# pmon_3v8.net
KiCad netlist of a schematic drawn in EAGLE
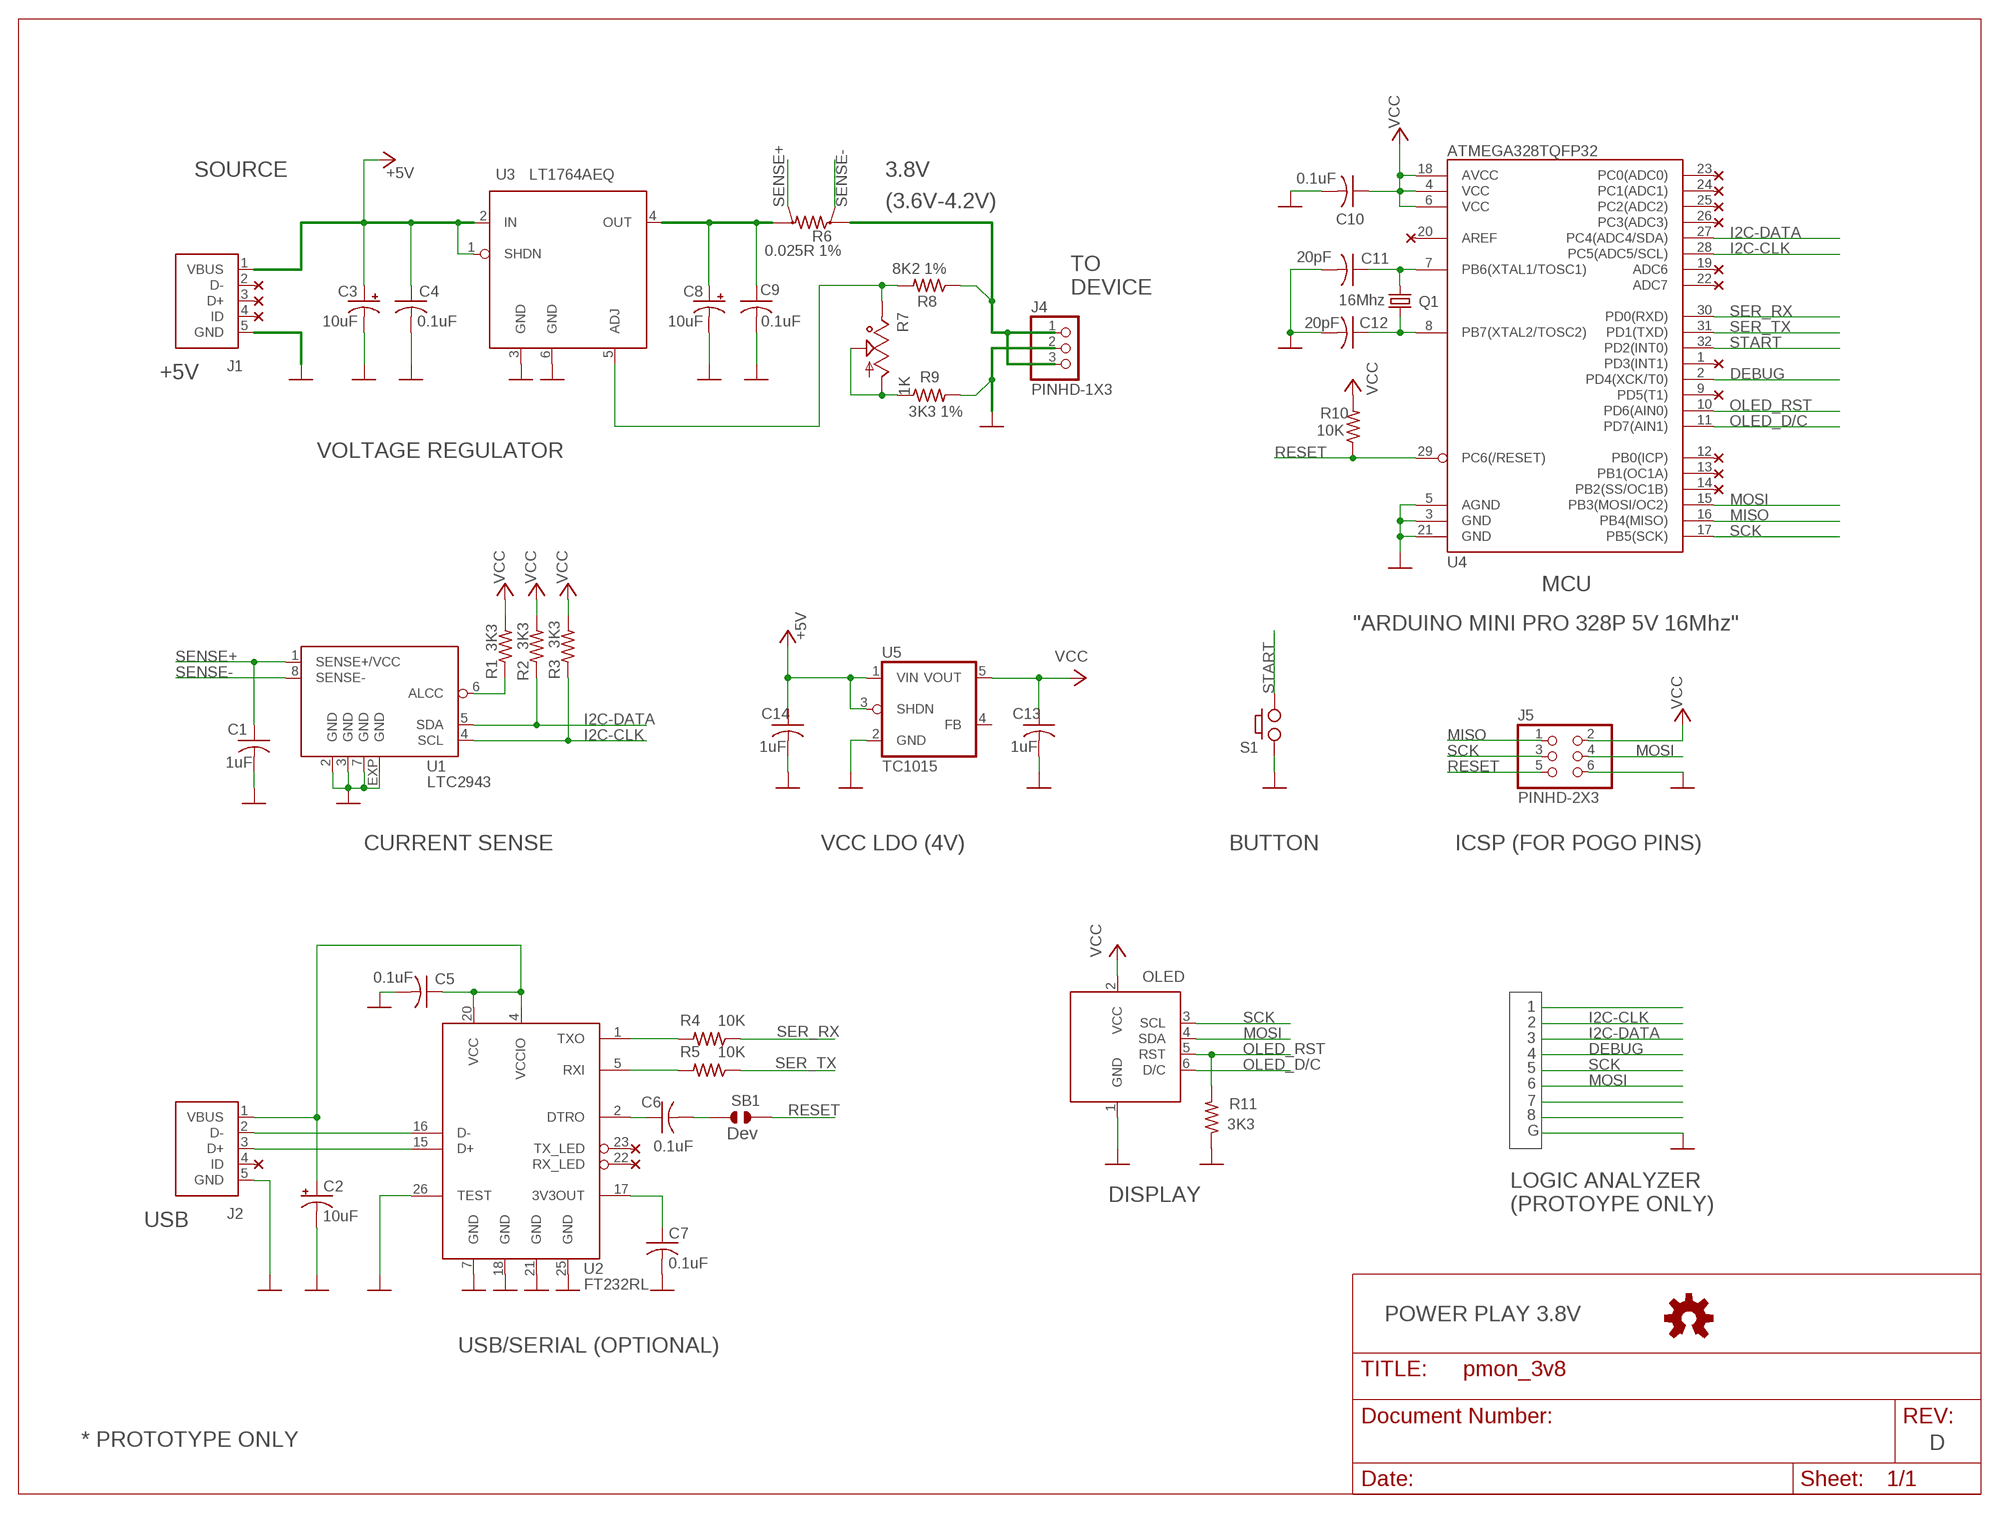
[diagram p0: schematic, sheet 1]

(export (version "E")
  (design (tool "Eeschema 10.0.6"))
  (components
    (comp (ref "C1")
      (value "1uF")
      (footprint "eagle-import:C0603")
      (libsource (lib "eagle-import") (part "CAP-C0603"))
    )
    (comp (ref "C2")
      (value "10uF")
      (footprint "eagle-import:A_3216-18R")
      (libsource (lib "eagle-import") (part "CPOL-USA/3216-18R"))
    )
    (comp (ref "C3")
      (value "10uF")
      (footprint "eagle-import:A_3216-18R")
      (libsource (lib "eagle-import") (part "CPOL-USA/3216-18R"))
    )
    (comp (ref "C4")
      (value "0.1uF")
      (footprint "eagle-import:C0603")
      (libsource (lib "eagle-import") (part "CAP-C0603"))
    )
    (comp (ref "C5")
      (value "0.1uF")
      (footprint "eagle-import:C0603")
      (libsource (lib "eagle-import") (part "CAP-C0603"))
    )
    (comp (ref "C6")
      (value "0.1uF")
      (footprint "eagle-import:C0603")
      (libsource (lib "eagle-import") (part "CAP-C0603"))
    )
    (comp (ref "C7")
      (value "0.1uF")
      (footprint "eagle-import:C0603")
      (libsource (lib "eagle-import") (part "CAP-C0603"))
    )
    (comp (ref "C8")
      (value "10uF")
      (footprint "eagle-import:A_3216-18R")
      (libsource (lib "eagle-import") (part "CPOL-USA/3216-18R"))
    )
    (comp (ref "C9")
      (value "0.1uF")
      (footprint "eagle-import:C0603")
      (libsource (lib "eagle-import") (part "CAP-C0603"))
    )
    (comp (ref "C10")
      (value "0.1uF")
      (footprint "eagle-import:C0603")
      (libsource (lib "eagle-import") (part "CAP-C0603"))
    )
    (comp (ref "C11")
      (value "20pF")
      (footprint "eagle-import:C0603")
      (libsource (lib "eagle-import") (part "CAP-C0603"))
    )
    (comp (ref "C12")
      (value "20pF")
      (footprint "eagle-import:C0603")
      (libsource (lib "eagle-import") (part "CAP-C0603"))
    )
    (comp (ref "C13")
      (value "1uF")
      (footprint "eagle-import:C0603")
      (libsource (lib "eagle-import") (part "CAP-C0603"))
    )
    (comp (ref "C14")
      (value "1uF")
      (footprint "eagle-import:C0603")
      (libsource (lib "eagle-import") (part "CAP-C0603"))
    )
    (comp (ref "J1")
      (value "USB")
      (footprint "eagle-import:USB-MICRO-ZX62RD-AB-5P8")
      (libsource (lib "eagle-import") (part "USB"))
    )
    (comp (ref "J2")
      (value "USB")
      (footprint "eagle-import:USB-MICRO-ZX62RD-AB-5P8")
      (libsource (lib "eagle-import") (part "USB"))
    )
    (comp (ref "J4")
      (value "PINHD-1X3")
      (footprint "eagle-import:1X03")
      (libsource (lib "eagle-import") (part "PINHD-1X3"))
    )
    (comp (ref "J5")
      (value "PINHD-2X3")
      (footprint "eagle-import:2X03")
      (libsource (lib "eagle-import") (part "PINHD-2X3"))
    )
    (comp (ref "OLED")
      (value "OLED")
      (footprint "eagle-import:OLED")
      (libsource (lib "eagle-import") (part "OLED"))
    )
    (comp (ref "Q1")
      (value "16Mhz")
      (footprint "eagle-import:CRYSTAL-CTS406")
      (libsource (lib "eagle-import") (part "CRYSTALCTS406"))
    )
    (comp (ref "R1")
      (value "3K3")
      (footprint "eagle-import:R0603")
      (libsource (lib "eagle-import") (part "RES-R0603"))
    )
    (comp (ref "R2")
      (value "3K3")
      (footprint "eagle-import:R0603")
      (libsource (lib "eagle-import") (part "RES-R0603"))
    )
    (comp (ref "R3")
      (value "3K3")
      (footprint "eagle-import:R0603")
      (libsource (lib "eagle-import") (part "RES-R0603"))
    )
    (comp (ref "R4")
      (value "10K")
      (footprint "eagle-import:R0603")
      (libsource (lib "eagle-import") (part "RES-R0603"))
    )
    (comp (ref "R5")
      (value "10K")
      (footprint "eagle-import:R0603")
      (libsource (lib "eagle-import") (part "RES-R0603"))
    )
    (comp (ref "R6")
      (value "0.025R 1%")
      (footprint "eagle-import:KELVIN-6432")
      (libsource (lib "eagle-import") (part "RES-SHUNT-6432"))
    )
    (comp (ref "R7")
      (value "1K")
      (footprint "eagle-import:TRIM-POT_SM-42_43A")
      (libsource (lib "eagle-import") (part "TRIM_US-SM-42/43A"))
    )
    (comp (ref "R8")
      (value "8K2 1%")
      (footprint "eagle-import:R0603")
      (libsource (lib "eagle-import") (part "RES-R0603"))
    )
    (comp (ref "R9")
      (value "3K3 1%")
      (footprint "eagle-import:R0603")
      (libsource (lib "eagle-import") (part "RES-R0603"))
    )
    (comp (ref "R10")
      (value "10K")
      (footprint "eagle-import:R0603")
      (libsource (lib "eagle-import") (part "RES-R0603"))
    )
    (comp (ref "R11")
      (value "3K3")
      (footprint "eagle-import:R0603")
      (libsource (lib "eagle-import") (part "RES-R0603"))
    )
    (comp (ref "S1")
      (value "PUSH_BUTTON")
      (footprint "eagle-import:TLE1105")
      (libsource (lib "eagle-import") (part "PUSH_BUTTON"))
    )
    (comp (ref "SB1")
      (value "JUMPER_SOLDER_1X2")
      (footprint "eagle-import:JUMPER_SOLDER_1X2")
      (libsource (lib "eagle-import") (part "JUMPER_SOLDER_1X2"))
    )
    (comp (ref "U$28")
      (value "OSH")
      (footprint "eagle-import:OSH")
      (libsource (lib "eagle-import") (part "OSH"))
    )
    (comp (ref "U1")
      (value "LTC2943")
      (footprint "eagle-import:DFN8-3X3")
      (libsource (lib "eagle-import") (part "LTC2943"))
    )
    (comp (ref "U2")
      (value "FT232RL")
      (footprint "eagle-import:SSOP28DB")
      (libsource (lib "eagle-import") (part "FT232RL"))
    )
    (comp (ref "U3")
      (value "LT1764AEQ")
      (footprint "eagle-import:TO263-5")
      (libsource (lib "eagle-import") (part "LTE1764"))
    )
    (comp (ref "U4")
      (value "ATMEGA328TQFP32")
      (footprint "eagle-import:TQFP32-08")
      (libsource (lib "eagle-import") (part "ATMEGA328TQFP32"))
    )
    (comp (ref "U5")
      (value "TC1015")
      (footprint "eagle-import:SOT25")
      (libsource (lib "eagle-import") (part "TC1015"))
    )
  )
  (nets
    (net (code "1") (name "+5V") (class "Default")
      (node (ref "C14") (pin "1") (pinfunction "1_1") (pintype "passive"))
      (node (ref "C3") (pin "+") (pinfunction "+_+") (pintype "passive"))
      (node (ref "C4") (pin "1") (pinfunction "1_1") (pintype "passive"))
      (node (ref "J1") (pin "1") (pinfunction "VBUS_1") (pintype "bidirectional"))
      (node (ref "U3") (pin "1") (pinfunction "SHDN_1") (pintype "bidirectional"))
      (node (ref "U3") (pin "2") (pinfunction "IN_2") (pintype "bidirectional"))
      (node (ref "U5") (pin "1") (pinfunction "VIN_1") (pintype "power_in"))
      (node (ref "U5") (pin "3") (pinfunction "SHDN_3") (pintype "input"))
    )
    (net (code "2") (name "/AREF") (class "Default")
      (node (ref "U4") (pin "20") (pinfunction "AREF_20") (pintype "power_in"))
    )
    (net (code "3") (name "/DEBUG") (class "Default")
      (node (ref "U4") (pin "2") (pinfunction "PD4(XCK/T0)_2") (pintype "bidirectional"))
    )
    (net (code "4") (name "/I2C-CLK") (class "Default")
      (node (ref "R3") (pin "1") (pinfunction "1_1") (pintype "passive"))
      (node (ref "U1") (pin "4") (pinfunction "SCL_4") (pintype "input"))
      (node (ref "U4") (pin "28") (pinfunction "PC5(ADC5/SCL)_28") (pintype "bidirectional"))
    )
    (net (code "5") (name "/I2C-DATA") (class "Default")
      (node (ref "R2") (pin "1") (pinfunction "1_1") (pintype "passive"))
      (node (ref "U1") (pin "5") (pinfunction "SDA_5") (pintype "bidirectional"))
      (node (ref "U4") (pin "27") (pinfunction "PC4(ADC4/SDA)_27") (pintype "bidirectional"))
    )
    (net (code "6") (name "/MISO") (class "Default")
      (node (ref "J5") (pin "1") (pinfunction "1_1") (pintype "passive"))
      (node (ref "U4") (pin "16") (pinfunction "PB4(MISO)_16") (pintype "bidirectional"))
    )
    (net (code "7") (name "/MOSI") (class "Default")
      (node (ref "J5") (pin "4") (pinfunction "4_4") (pintype "passive"))
      (node (ref "OLED") (pin "4") (pinfunction "SDA_4") (pintype "input"))
      (node (ref "U4") (pin "15") (pinfunction "PB3(MOSI/OC2)_15") (pintype "bidirectional"))
    )
    (net (code "8") (name "/OLED_D{slash}C") (class "Default")
      (node (ref "OLED") (pin "6") (pinfunction "D/C_6") (pintype "input"))
      (node (ref "U4") (pin "11") (pinfunction "PD7(AIN1)_11") (pintype "bidirectional"))
    )
    (net (code "9") (name "/OLED_RST") (class "Default")
      (node (ref "OLED") (pin "5") (pinfunction "RST_5") (pintype "input"))
      (node (ref "R11") (pin "2") (pinfunction "2_2") (pintype "passive"))
      (node (ref "U4") (pin "10") (pinfunction "PD6(AIN0)_10") (pintype "bidirectional"))
    )
    (net (code "10") (name "/RESET") (class "Default")
      (node (ref "J5") (pin "5") (pinfunction "5_5") (pintype "passive"))
      (node (ref "R10") (pin "1") (pinfunction "1_1") (pintype "passive"))
      (node (ref "SB1") (pin "2") (pinfunction "2_2") (pintype "passive"))
      (node (ref "U4") (pin "29") (pinfunction "PC6(/RESET)_29") (pintype "bidirectional"))
    )
    (net (code "11") (name "/SCK") (class "Default")
      (node (ref "J5") (pin "3") (pinfunction "3_3") (pintype "passive"))
      (node (ref "OLED") (pin "3") (pinfunction "SCL_3") (pintype "input"))
      (node (ref "U4") (pin "17") (pinfunction "PB5(SCK)_17") (pintype "bidirectional"))
    )
    (net (code "12") (name "/SENSE+") (class "Default")
      (node (ref "C1") (pin "1") (pinfunction "1_1") (pintype "passive"))
      (node (ref "R6") (pin "V2") (pinfunction "V2_V2") (pintype "passive"))
      (node (ref "U1") (pin "1") (pinfunction "SENSE+/VCC_1") (pintype "passive"))
    )
    (net (code "13") (name "/SENSE-") (class "Default")
      (node (ref "R6") (pin "V1") (pinfunction "V1_V1") (pintype "passive"))
      (node (ref "U1") (pin "8") (pinfunction "SENSE-_8") (pintype "passive"))
    )
    (net (code "14") (name "/SER_RX") (class "Default")
      (node (ref "R4") (pin "1") (pinfunction "1_1") (pintype "passive"))
      (node (ref "U4") (pin "30") (pinfunction "PD0(RXD)_30") (pintype "bidirectional"))
    )
    (net (code "15") (name "/SER_TX") (class "Default")
      (node (ref "R5") (pin "1") (pinfunction "1_1") (pintype "passive"))
      (node (ref "U4") (pin "31") (pinfunction "PD1(TXD)_31") (pintype "bidirectional"))
    )
    (net (code "16") (name "/START") (class "Default")
      (node (ref "S1") (pin "B") (pinfunction "2_B") (pintype "passive"))
      (node (ref "U4") (pin "32") (pinfunction "PD2(INT0)_32") (pintype "bidirectional"))
    )
    (net (code "17") (name "GND") (class "Default")
      (node (ref "C1") (pin "2") (pinfunction "2_2") (pintype "passive"))
      (node (ref "C10") (pin "2") (pinfunction "2_2") (pintype "passive"))
      (node (ref "C11") (pin "2") (pinfunction "2_2") (pintype "passive"))
      (node (ref "C12") (pin "2") (pinfunction "2_2") (pintype "passive"))
      (node (ref "C13") (pin "2") (pinfunction "2_2") (pintype "passive"))
      (node (ref "C14") (pin "2") (pinfunction "2_2") (pintype "passive"))
      (node (ref "C2") (pin "-") (pinfunction "-_-") (pintype "passive"))
      (node (ref "C3") (pin "-") (pinfunction "-_-") (pintype "passive"))
      (node (ref "C4") (pin "2") (pinfunction "2_2") (pintype "passive"))
      (node (ref "C5") (pin "2") (pinfunction "2_2") (pintype "passive"))
      (node (ref "C7") (pin "2") (pinfunction "2_2") (pintype "passive"))
      (node (ref "C8") (pin "-") (pinfunction "-_-") (pintype "passive"))
      (node (ref "C9") (pin "2") (pinfunction "2_2") (pintype "passive"))
      (node (ref "J1") (pin "5") (pinfunction "GND_5") (pintype "bidirectional"))
      (node (ref "J2") (pin "5") (pinfunction "GND_5") (pintype "bidirectional"))
      (node (ref "J4") (pin "2") (pinfunction "2_2") (pintype "passive"))
      (node (ref "J5") (pin "6") (pinfunction "6_6") (pintype "passive"))
      (node (ref "OLED") (pin "1") (pinfunction "GND_1") (pintype "power_in"))
      (node (ref "R11") (pin "1") (pinfunction "1_1") (pintype "passive"))
      (node (ref "R9") (pin "2") (pinfunction "2_2") (pintype "passive"))
      (node (ref "S1") (pin "A") (pinfunction "1_A") (pintype "passive"))
      (node (ref "U1") (pin "2") (pinfunction "GND_2") (pintype "power_in"))
      (node (ref "U1") (pin "3") (pinfunction "GND_3") (pintype "power_in"))
      (node (ref "U1") (pin "7") (pinfunction "GND_7") (pintype "power_in"))
      (node (ref "U1") (pin "EXP") (pinfunction "GND_EXP") (pintype "power_in"))
      (node (ref "U2") (pin "18") (pinfunction "GND_18") (pintype "power_in"))
      (node (ref "U2") (pin "21") (pinfunction "GND_21") (pintype "power_in"))
      (node (ref "U2") (pin "25") (pinfunction "GND_25") (pintype "power_in"))
      (node (ref "U2") (pin "26") (pinfunction "TEST_26") (pintype "input"))
      (node (ref "U2") (pin "7") (pinfunction "GND_7") (pintype "power_in"))
      (node (ref "U3") (pin "3") (pinfunction "GND_3") (pintype "bidirectional"))
      (node (ref "U3") (pin "6") (pinfunction "GND_6") (pintype "bidirectional"))
      (node (ref "U4") (pin "21") (pinfunction "GND_21") (pintype "power_in"))
      (node (ref "U4") (pin "3") (pinfunction "GND_3") (pintype "power_in"))
      (node (ref "U4") (pin "5") (pinfunction "AGND_5") (pintype "power_in"))
      (node (ref "U5") (pin "2") (pinfunction "GND_2") (pintype "power_in"))
    )
    (net (code "18") (name "Net-(C6-Pad2)") (class "Default")
      (node (ref "C6") (pin "2") (pinfunction "2_2") (pintype "passive"))
      (node (ref "SB1") (pin "1") (pinfunction "1_1") (pintype "passive"))
    )
    (net (code "19") (name "Net-(J2-D+)") (class "Default")
      (node (ref "J2") (pin "3") (pinfunction "D+_3") (pintype "bidirectional"))
      (node (ref "U2") (pin "15") (pinfunction "D+_15") (pintype "passive"))
    )
    (net (code "20") (name "Net-(J2-D-)") (class "Default")
      (node (ref "J2") (pin "2") (pinfunction "D-_2") (pintype "bidirectional"))
      (node (ref "U2") (pin "16") (pinfunction "D-_16") (pintype "passive"))
    )
    (net (code "21") (name "Net-(J2-VBUS)") (class "Default")
      (node (ref "C2") (pin "+") (pinfunction "+_+") (pintype "passive"))
      (node (ref "C5") (pin "1") (pinfunction "1_1") (pintype "passive"))
      (node (ref "J2") (pin "1") (pinfunction "VBUS_1") (pintype "bidirectional"))
      (node (ref "U2") (pin "20") (pinfunction "VCC_20") (pintype "power_in"))
      (node (ref "U2") (pin "4") (pinfunction "VCCIO_4") (pintype "power_in"))
    )
    (net (code "22") (name "Net-(J4-Pad1)") (class "Default")
      (node (ref "J4") (pin "1") (pinfunction "1_1") (pintype "passive"))
      (node (ref "J4") (pin "3") (pinfunction "3_3") (pintype "passive"))
      (node (ref "R6") (pin "I1") (pinfunction "I1_I1") (pintype "passive"))
      (node (ref "R8") (pin "1") (pinfunction "1_1") (pintype "passive"))
    )
    (net (code "23") (name "Net-(Q1-2)") (class "Default")
      (node (ref "C12") (pin "1") (pinfunction "1_1") (pintype "passive"))
      (node (ref "Q1") (pin "3") (pinfunction "2_3") (pintype "passive"))
      (node (ref "U4") (pin "8") (pinfunction "PB7(XTAL2/TOSC2)_8") (pintype "bidirectional"))
    )
    (net (code "24") (name "Net-(R7-Pad1)") (class "Default")
      (node (ref "R7") (pin "1") (pinfunction "1_1") (pintype "passive"))
      (node (ref "R7") (pin "2") (pinfunction "2_2") (pintype "passive"))
      (node (ref "R9") (pin "1") (pinfunction "1_1") (pintype "passive"))
    )
    (net (code "25") (name "Net-(U1-ALCC)") (class "Default")
      (node (ref "R1") (pin "1") (pinfunction "1_1") (pintype "passive"))
      (node (ref "U1") (pin "6") (pinfunction "ALCC_6") (pintype "open_collector"))
    )
    (net (code "26") (name "Net-(U2-3V3OUT)") (class "Default")
      (node (ref "C7") (pin "1") (pinfunction "1_1") (pintype "passive"))
      (node (ref "U2") (pin "17") (pinfunction "3V3OUT_17") (pintype "power_in"))
    )
    (net (code "27") (name "Net-(U2-DTRO)") (class "Default")
      (node (ref "C6") (pin "1") (pinfunction "1_1") (pintype "passive"))
      (node (ref "U2") (pin "2") (pinfunction "DTRO_2") (pintype "output"))
    )
    (net (code "28") (name "Net-(U2-RXI)") (class "Default")
      (node (ref "R5") (pin "2") (pinfunction "2_2") (pintype "passive"))
      (node (ref "U2") (pin "5") (pinfunction "RXI_5") (pintype "input"))
    )
    (net (code "29") (name "Net-(U2-TXO)") (class "Default")
      (node (ref "R4") (pin "2") (pinfunction "2_2") (pintype "passive"))
      (node (ref "U2") (pin "1") (pinfunction "TXO_1") (pintype "output"))
    )
    (net (code "30") (name "Net-(U3-ADJ)") (class "Default")
      (node (ref "R7") (pin "3") (pinfunction "3_3") (pintype "passive"))
      (node (ref "R8") (pin "2") (pinfunction "2_2") (pintype "passive"))
      (node (ref "U3") (pin "5") (pinfunction "ADJ_5") (pintype "bidirectional"))
    )
    (net (code "31") (name "Net-(U3-OUT)") (class "Default")
      (node (ref "C8") (pin "+") (pinfunction "+_+") (pintype "passive"))
      (node (ref "C9") (pin "1") (pinfunction "1_1") (pintype "passive"))
      (node (ref "R6") (pin "I2") (pinfunction "I2_I2") (pintype "passive"))
      (node (ref "U3") (pin "4") (pinfunction "OUT_4") (pintype "bidirectional"))
    )
    (net (code "32") (name "Net-(U4-PB6(XTAL1{slash}TOSC1))") (class "Default")
      (node (ref "C11") (pin "1") (pinfunction "1_1") (pintype "passive"))
      (node (ref "Q1") (pin "1") (pinfunction "1_1") (pintype "passive"))
      (node (ref "U4") (pin "7") (pinfunction "PB6(XTAL1/TOSC1)_7") (pintype "bidirectional"))
    )
    (net (code "33") (name "VCC") (class "Default")
      (node (ref "C10") (pin "1") (pinfunction "1_1") (pintype "passive"))
      (node (ref "C13") (pin "1") (pinfunction "1_1") (pintype "passive"))
      (node (ref "J5") (pin "2") (pinfunction "2_2") (pintype "passive"))
      (node (ref "OLED") (pin "2") (pinfunction "VCC_2") (pintype "power_in"))
      (node (ref "R1") (pin "2") (pinfunction "2_2") (pintype "passive"))
      (node (ref "R10") (pin "2") (pinfunction "2_2") (pintype "passive"))
      (node (ref "R2") (pin "2") (pinfunction "2_2") (pintype "passive"))
      (node (ref "R3") (pin "2") (pinfunction "2_2") (pintype "passive"))
      (node (ref "U4") (pin "18") (pinfunction "AVCC_18") (pintype "power_in"))
      (node (ref "U4") (pin "4") (pinfunction "VCC_4") (pintype "power_in"))
      (node (ref "U4") (pin "6") (pinfunction "VCC_6") (pintype "power_in"))
      (node (ref "U5") (pin "5") (pinfunction "VOUT_5") (pintype "power_in"))
    )
    (net (code "34") (name "unconnected-(J1-D+-Pad3)") (class "Default")
      (node (ref "J1") (pin "3") (pinfunction "D+_3") (pintype "bidirectional"))
    )
    (net (code "35") (name "unconnected-(J1-D--Pad2)") (class "Default")
      (node (ref "J1") (pin "2") (pinfunction "D-_2") (pintype "bidirectional"))
    )
    (net (code "36") (name "unconnected-(J1-ID-Pad4)") (class "Default")
      (node (ref "J1") (pin "4") (pinfunction "ID_4") (pintype "bidirectional"))
    )
    (net (code "37") (name "unconnected-(J2-ID-Pad4)") (class "Default")
      (node (ref "J2") (pin "4") (pinfunction "ID_4") (pintype "bidirectional"))
    )
    (net (code "38") (name "unconnected-(U2-RX_LED-Pad22)") (class "Default")
      (node (ref "U2") (pin "22") (pinfunction "RX_LED_22") (pintype "output"))
    )
    (net (code "39") (name "unconnected-(U2-TX_LED-Pad23)") (class "Default")
      (node (ref "U2") (pin "23") (pinfunction "TX_LED_23") (pintype "output"))
    )
    (net (code "40") (name "unconnected-(U4-ADC6-Pad19)") (class "Default")
      (node (ref "U4") (pin "19") (pinfunction "ADC6_19") (pintype "bidirectional"))
    )
    (net (code "41") (name "unconnected-(U4-ADC7-Pad22)") (class "Default")
      (node (ref "U4") (pin "22") (pinfunction "ADC7_22") (pintype "bidirectional"))
    )
    (net (code "42") (name "unconnected-(U4-PB0(ICP)-Pad12)") (class "Default")
      (node (ref "U4") (pin "12") (pinfunction "PB0(ICP)_12") (pintype "bidirectional"))
    )
    (net (code "43") (name "unconnected-(U4-PB1(OC1A)-Pad13)") (class "Default")
      (node (ref "U4") (pin "13") (pinfunction "PB1(OC1A)_13") (pintype "bidirectional"))
    )
    (net (code "44") (name "unconnected-(U4-PB2(SS{slash}OC1B)-Pad14)") (class "Default")
      (node (ref "U4") (pin "14") (pinfunction "PB2(SS/OC1B)_14") (pintype "bidirectional"))
    )
    (net (code "45") (name "unconnected-(U4-PC0(ADC0)-Pad23)") (class "Default")
      (node (ref "U4") (pin "23") (pinfunction "PC0(ADC0)_23") (pintype "bidirectional"))
    )
    (net (code "46") (name "unconnected-(U4-PC1(ADC1)-Pad24)") (class "Default")
      (node (ref "U4") (pin "24") (pinfunction "PC1(ADC1)_24") (pintype "bidirectional"))
    )
    (net (code "47") (name "unconnected-(U4-PC2(ADC2)-Pad25)") (class "Default")
      (node (ref "U4") (pin "25") (pinfunction "PC2(ADC2)_25") (pintype "bidirectional"))
    )
    (net (code "48") (name "unconnected-(U4-PC3(ADC3)-Pad26)") (class "Default")
      (node (ref "U4") (pin "26") (pinfunction "PC3(ADC3)_26") (pintype "bidirectional"))
    )
    (net (code "49") (name "unconnected-(U4-PD3(INT1)-Pad1)") (class "Default")
      (node (ref "U4") (pin "1") (pinfunction "PD3(INT1)_1") (pintype "bidirectional"))
    )
    (net (code "50") (name "unconnected-(U4-PD5(T1)-Pad9)") (class "Default")
      (node (ref "U4") (pin "9") (pinfunction "PD5(T1)_9") (pintype "bidirectional"))
    )
    (net (code "51") (name "unconnected-(U5-FB-Pad4)") (class "Default")
      (node (ref "U5") (pin "4") (pinfunction "FB_4") (pintype "input"))
    )
  )
)
